# Arduino_Shield_2.net
KiCad netlist of a schematic drawn in Altium Designer
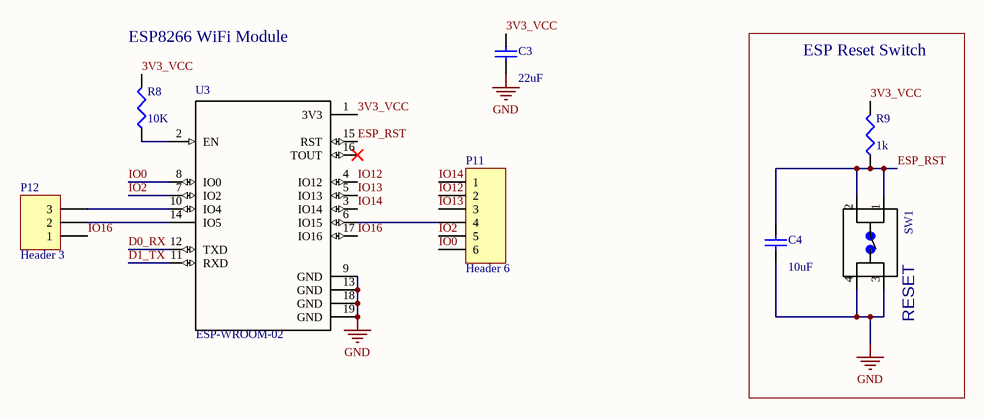
[diagram p0: Arduino_Shield_2.SchDoc]

(export (version "E")
  (design (tool "Eeschema 10.0.6"))
  (components
    (comp (ref "C3")
      (value "22uF")
      (footprint "C1206")
      (description "Capacitor (Semiconductor SIM Model)")
      (fields
        (field (name "DIGIKEYPARTNO") "1276-1079-1-ND")
        (field (name "Comment") "Cap Semi")
        (field (name "PUBLISHER") "Altium Limited")
      )
      (libsource (lib "Miscellaneous Devices") (part "Cap Semi"))
    )
    (comp (ref "C4")
      (value "10uF")
      (footprint "C1206")
      (description "Capacitor (Semiconductor SIM Model)")
      (fields
        (field (name "DIGIKEYPARTNO") "1276-1079-1-ND")
        (field (name "Comment") "Cap Semi")
        (field (name "PUBLISHER") "Altium Limited")
      )
      (libsource (lib "Miscellaneous Devices") (part "Cap Semi"))
    )
    (comp (ref "P11")
      (value "Header 6")
      (footprint "HDR1X6")
      (description "Header, 6-Pin")
      (fields (field (name "DIGIKEYPARTNO") "1212-1179-ND") (field (name "PUBLISHER") "Altium Limited"))
      (libsource (lib "Miscellaneous Connectors") (part "Header 6"))
    )
    (comp (ref "P12")
      (value "Header 3")
      (footprint "HDR1X3")
      (description "Header, 3-Pin")
      (fields (field (name "DIGIKEYPARTNO") "1212-1179-ND") (field (name "PUBLISHER") "Altium Limited"))
      (libsource (lib "Miscellaneous Connectors") (part "Header 3"))
    )
    (comp (ref "R8")
      (value "10K")
      (footprint "C1206")
      (description "Resistor")
      (fields
        (field (name "DIGIKEYPARTNO") "RMCF1206JT10K0CT-ND")
        (field (name "Comment") "Res3")
        (field (name "PUBLISHER") "Altium Limited")
      )
      (libsource (lib "Miscellaneous Devices") (part "Res3"))
    )
    (comp (ref "R9")
      (value "1k")
      (footprint "C1206")
      (description "Resistor")
      (fields
        (field (name "DIGIKEYPARTNO") "RNCP1206FTD1K00CT-ND")
        (field (name "Comment") "Res3")
        (field (name "PUBLISHER") "Altium Limited")
      )
      (libsource (lib "Miscellaneous Devices") (part "Res3"))
    )
    (comp (ref "SW1")
      (value "RESET")
      (footprint "*TE_FSM4JSMA")
      (description "FSM4JSMA=SMT,TACTILE,PB SWITCH")
      (fields (field (name "MF") "TE Connectivity") (field (name "MP") "FSM4JSMA"))
      (libsource (lib "FSM4JSMA") (part "FSM4JSMA"))
    )
    (comp (ref "U3")
      (value "ESP-WROOM-02")
      (footprint "*MODULE_ESP-WROOM-02")
      (description "Wi-Fi Module w/ESP8266 802.11b/g/n 20dBm 20x18x3mm")
      (fields (field (name "MF") "Espressif Systems") (field (name "DIGIKEYPARTNO") "1904-1021-1-ND"))
      (libsource (lib "ESP-WROOM-02") (part "ESP-WROOM-02"))
    )
  )
  (nets
    (net (code "1") (name "/3V3_VCC") (class "Default")
      (node (ref "C3") (pin "2") (pinfunction "2_2") (pintype "passive"))
      (node (ref "R8") (pin "2") (pinfunction "2_2") (pintype "passive"))
      (node (ref "R9") (pin "2") (pinfunction "2_2") (pintype "passive"))
      (node (ref "U3") (pin "1") (pinfunction "3V3_1") (pintype "power_in"))
    )
    (net (code "2") (name "/D0_RX") (class "Default")
      (node (ref "U3") (pin "12") (pinfunction "TXD_12") (pintype "bidirectional"))
    )
    (net (code "3") (name "/D1_TX") (class "Default")
      (node (ref "U3") (pin "11") (pinfunction "RXD_11") (pintype "bidirectional"))
    )
    (net (code "4") (name "/ESP_RST") (class "Default")
      (node (ref "C4") (pin "2") (pinfunction "2_2") (pintype "passive"))
      (node (ref "R9") (pin "1") (pinfunction "1_1") (pintype "passive"))
      (node (ref "SW1") (pin "1") (pinfunction "1_1") (pintype "passive"))
      (node (ref "SW1") (pin "2") (pinfunction "2_2") (pintype "passive"))
      (node (ref "U3") (pin "15") (pinfunction "RST_15") (pintype "bidirectional"))
    )
    (net (code "5") (name "/IO0") (class "Default")
      (node (ref "P11") (pin "6") (pinfunction "6_6") (pintype "passive"))
      (node (ref "U3") (pin "8") (pinfunction "IO0_8") (pintype "bidirectional"))
    )
    (net (code "6") (name "/IO2") (class "Default")
      (node (ref "P11") (pin "5") (pinfunction "5_5") (pintype "passive"))
      (node (ref "U3") (pin "7") (pinfunction "IO2_7") (pintype "bidirectional"))
    )
    (net (code "7") (name "/IO12") (class "Default")
      (node (ref "P11") (pin "2") (pinfunction "2_2") (pintype "passive"))
      (node (ref "U3") (pin "4") (pinfunction "IO12_4") (pintype "bidirectional"))
    )
    (net (code "8") (name "/IO13") (class "Default")
      (node (ref "P11") (pin "3") (pinfunction "3_3") (pintype "passive"))
      (node (ref "U3") (pin "5") (pinfunction "IO13_5") (pintype "bidirectional"))
    )
    (net (code "9") (name "/IO14") (class "Default")
      (node (ref "P11") (pin "1") (pinfunction "1_1") (pintype "passive"))
      (node (ref "U3") (pin "3") (pinfunction "IO14_3") (pintype "bidirectional"))
    )
    (net (code "10") (name "/IO16") (class "Default")
      (node (ref "P12") (pin "1") (pinfunction "1_1") (pintype "passive"))
      (node (ref "U3") (pin "17") (pinfunction "IO16_17") (pintype "bidirectional"))
    )
    (net (code "11") (name "GND") (class "Default")
      (node (ref "C3") (pin "1") (pinfunction "1_1") (pintype "passive"))
      (node (ref "C4") (pin "1") (pinfunction "1_1") (pintype "passive"))
      (node (ref "SW1") (pin "3") (pinfunction "3_3") (pintype "passive"))
      (node (ref "SW1") (pin "4") (pinfunction "4_4") (pintype "passive"))
      (node (ref "U3") (pin "13") (pinfunction "GND_13") (pintype "power_in"))
      (node (ref "U3") (pin "18") (pinfunction "GND_18") (pintype "power_in"))
      (node (ref "U3") (pin "19") (pinfunction "GND_19") (pintype "power_in"))
      (node (ref "U3") (pin "9") (pinfunction "GND_9") (pintype "power_in"))
    )
    (net (code "12") (name "Net-(U3-EN)") (class "Default")
      (node (ref "R8") (pin "1") (pinfunction "1_1") (pintype "passive"))
      (node (ref "U3") (pin "2") (pinfunction "EN_2") (pintype "input"))
    )
    (net (code "13") (name "Net-(U3-IO4)") (class "Default")
      (node (ref "P12") (pin "3") (pinfunction "3_3") (pintype "passive"))
      (node (ref "U3") (pin "10") (pinfunction "IO4_10") (pintype "bidirectional"))
    )
    (net (code "14") (name "Net-(U3-IO5)") (class "Default")
      (node (ref "P12") (pin "2") (pinfunction "2_2") (pintype "passive"))
      (node (ref "U3") (pin "14") (pinfunction "IO5_14") (pintype "open_collector"))
    )
    (net (code "15") (name "Net-(U3-IO15)") (class "Default")
      (node (ref "P11") (pin "4") (pinfunction "4_4") (pintype "passive"))
      (node (ref "U3") (pin "6") (pinfunction "IO15_6") (pintype "bidirectional"))
    )
    (net (code "16") (name "unconnected-(U3-TOUT-Pad16)") (class "Default")
      (node (ref "U3") (pin "16") (pinfunction "TOUT_16") (pintype "bidirectional+no_connect"))
    )
  )
)
